# LED_Indicator.net
KiCad netlist of a schematic drawn in Altium Designer
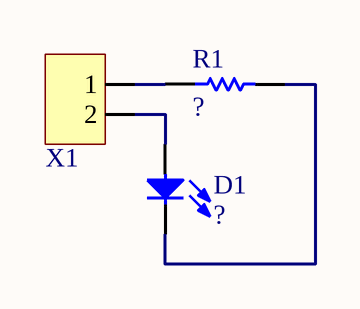
[diagram p0: LED_Indicator.SchDoc]

(export (version "E")
  (design (tool "Eeschema 10.0.6"))
  (components
    (comp (ref "D1")
      (value "?")
      (footprint "LED_2835")
      (libsource (lib "COMPONENTS_2022") (part "Diode LED"))
    )
    (comp (ref "R1")
      (value "Resistor")
      (footprint "RES_0603")
      (fields (field (name "RESISTANCE") "?"))
      (libsource (lib "COMPONENTS_2022") (part "Resistor"))
    )
    (comp (ref "X1")
      (value "?")
      (footprint "PAD_SMD_X2")
      (libsource (lib "COMPONENTS_2022") (part "Double connector"))
    )
  )
  (nets
    (net (code "1") (name "Net-(D1-A)") (class "Default")
      (node (ref "D1") (pin "1") (pinfunction "A_1") (pintype "passive"))
      (node (ref "X1") (pin "2") (pinfunction "2_2") (pintype "passive"))
    )
    (net (code "2") (name "Net-(D1-K)") (class "Default")
      (node (ref "D1") (pin "2") (pinfunction "K_2") (pintype "passive"))
      (node (ref "R1") (pin "2") (pinfunction "2_2") (pintype "passive"))
    )
    (net (code "3") (name "Net-(R1-Pad1)") (class "Default")
      (node (ref "R1") (pin "1") (pinfunction "1_1") (pintype "passive"))
      (node (ref "X1") (pin "1") (pinfunction "1_1") (pintype "passive"))
    )
  )
)
